# main.net
KiCad netlist of a schematic drawn in EAGLE
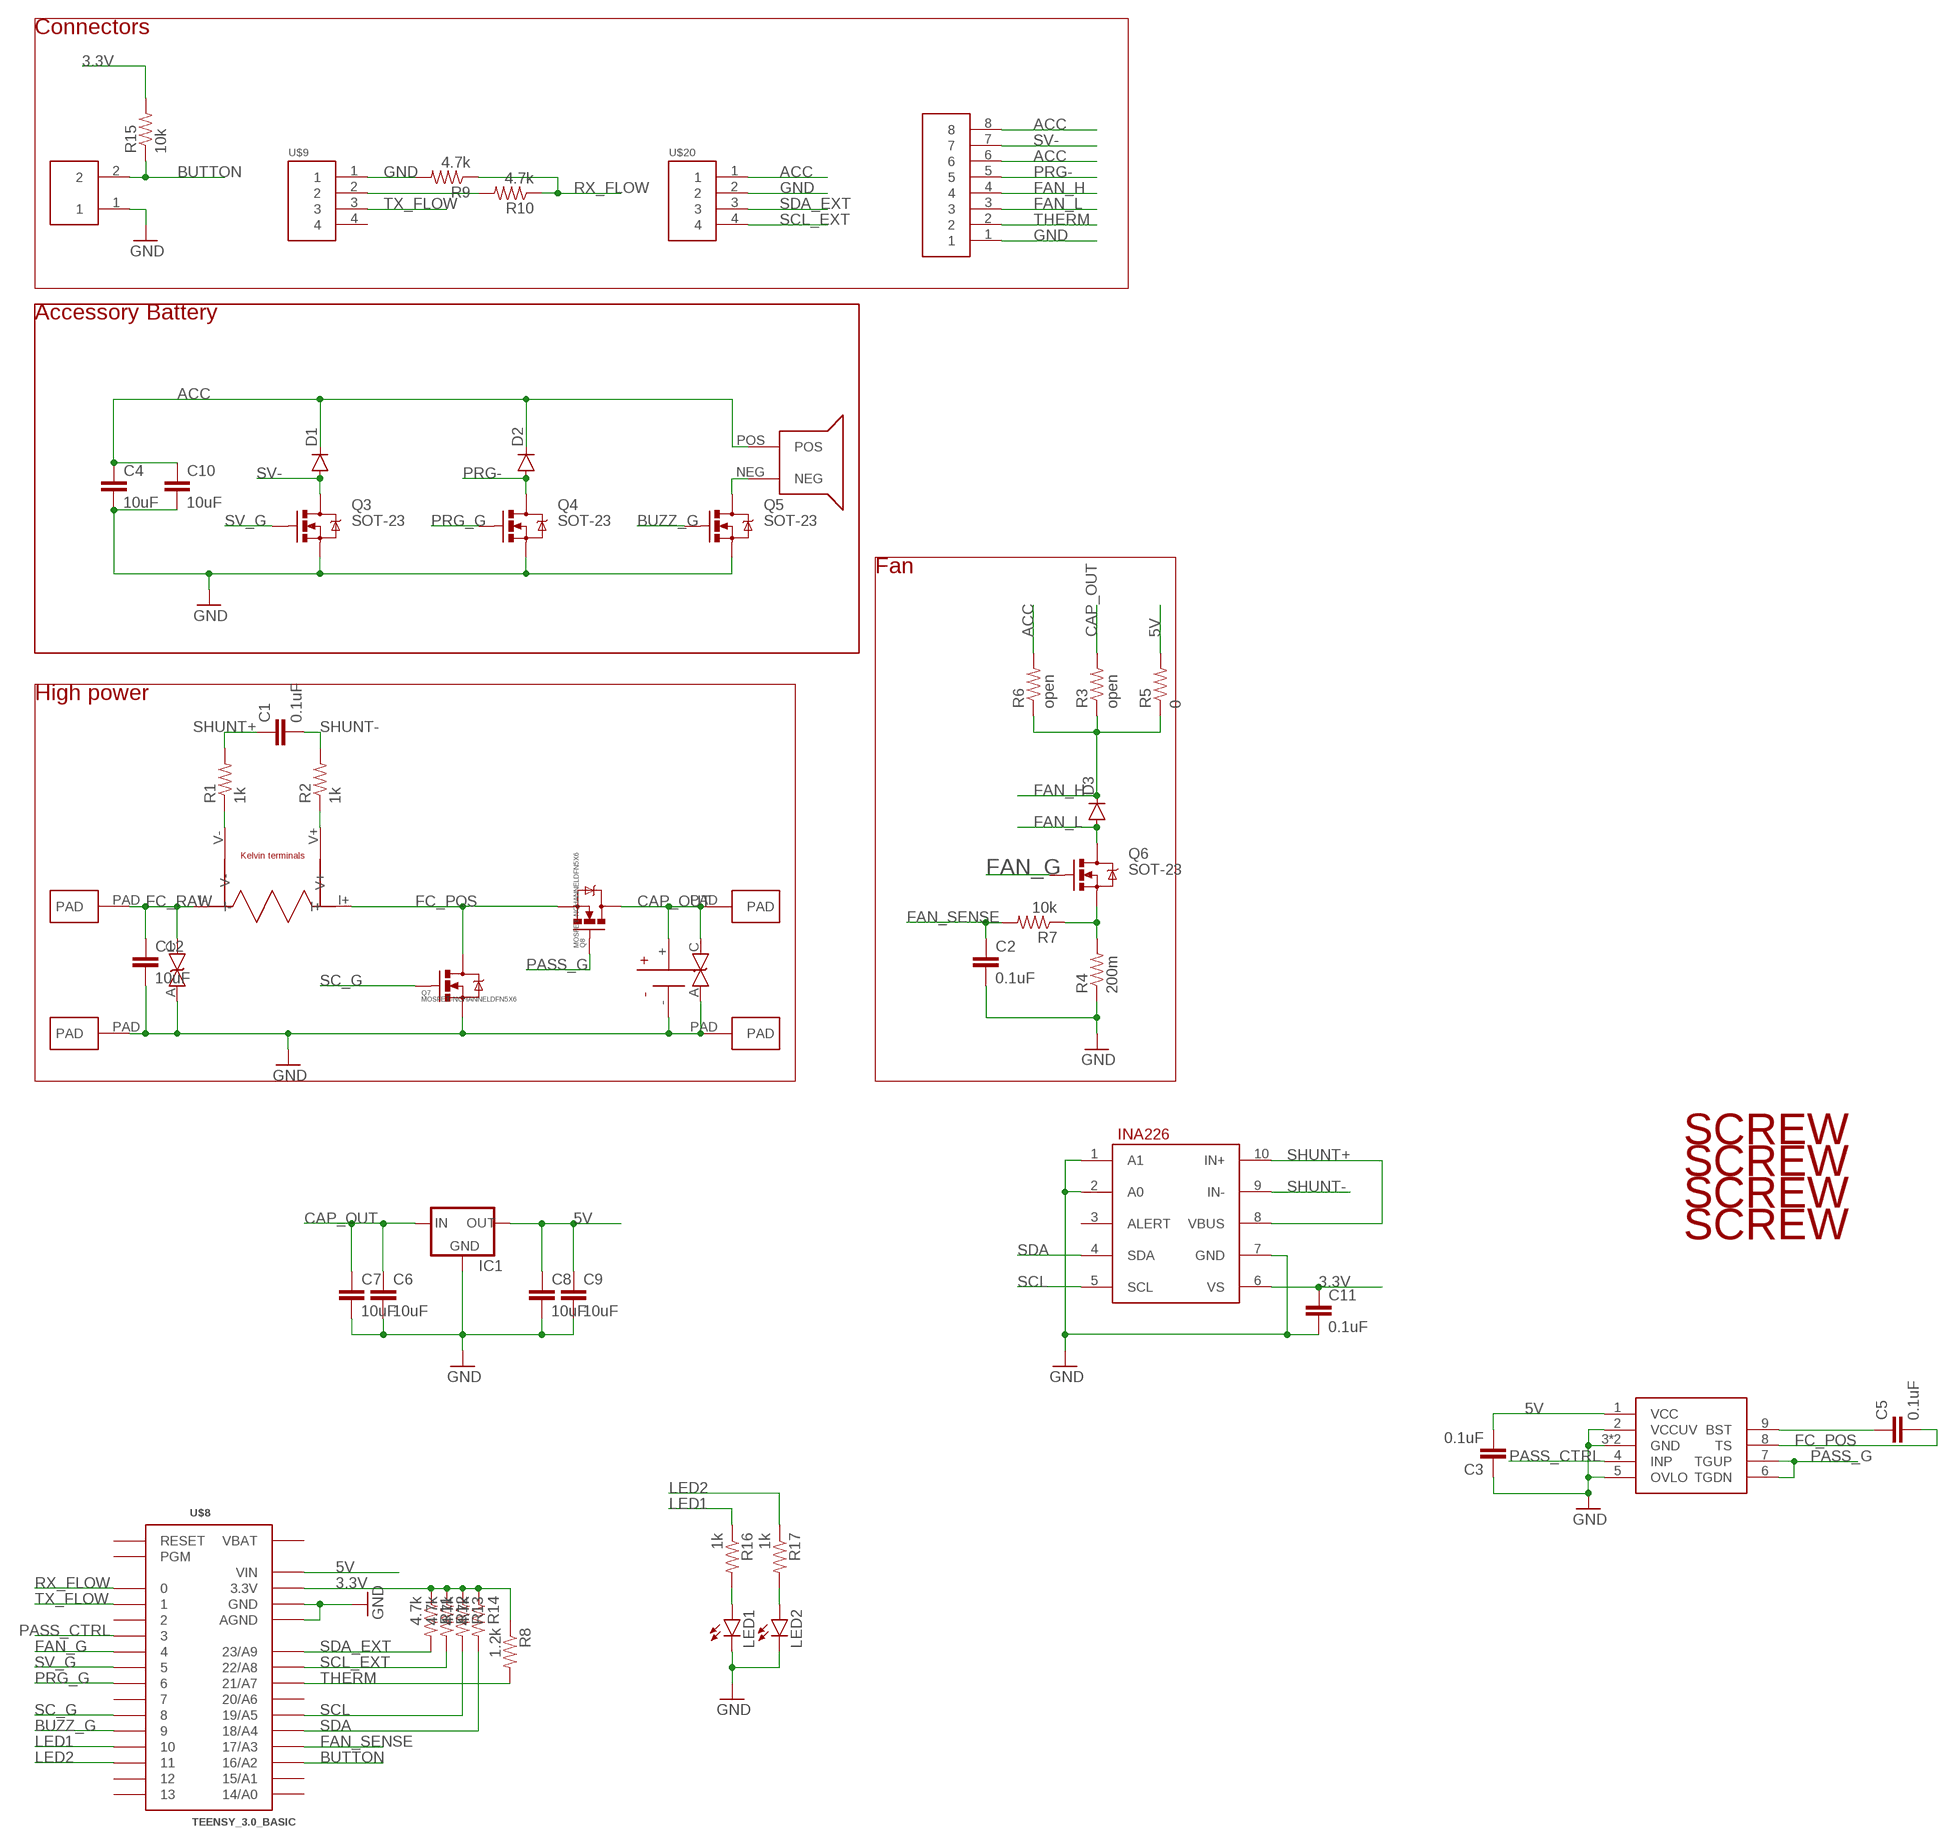
[diagram p0: schematic, sheet 1]

(export (version "E")
  (design (tool "Eeschema 10.0.6"))
  (components
    (comp (ref "C1")
      (value "0.1uF")
      (footprint "eagle-import:0603-CAP")
      (libsource (lib "eagle-import") (part "CAP0603-CAP"))
    )
    (comp (ref "C2")
      (value "0.1uF")
      (footprint "eagle-import:0603-CAP")
      (libsource (lib "eagle-import") (part "CAP0603-CAP"))
    )
    (comp (ref "C3")
      (value "0.1uF")
      (footprint "eagle-import:0603-CAP")
      (libsource (lib "eagle-import") (part "CAP0603-CAP"))
    )
    (comp (ref "C4")
      (value "10uF")
      (footprint "eagle-import:1206")
      (libsource (lib "eagle-import") (part "CAP1206"))
    )
    (comp (ref "C5")
      (value "0.1uF")
      (footprint "eagle-import:0603-CAP")
      (libsource (lib "eagle-import") (part "CAP0603-CAP"))
    )
    (comp (ref "C6")
      (value "10uF")
      (footprint "eagle-import:1206")
      (libsource (lib "eagle-import") (part "CAP1206"))
    )
    (comp (ref "C7")
      (value "10uF")
      (footprint "eagle-import:1206")
      (libsource (lib "eagle-import") (part "CAP1206"))
    )
    (comp (ref "C8")
      (value "10uF")
      (footprint "eagle-import:1206")
      (libsource (lib "eagle-import") (part "CAP1206"))
    )
    (comp (ref "C9")
      (value "10uF")
      (footprint "eagle-import:1206")
      (libsource (lib "eagle-import") (part "CAP1206"))
    )
    (comp (ref "C10")
      (value "10uF")
      (footprint "eagle-import:1206")
      (libsource (lib "eagle-import") (part "CAP1206"))
    )
    (comp (ref "C11")
      (value "0.1uF")
      (footprint "eagle-import:0603-CAP")
      (libsource (lib "eagle-import") (part "CAP0603-CAP"))
    )
    (comp (ref "C12")
      (value "10uF")
      (footprint "eagle-import:1206")
      (libsource (lib "eagle-import") (part "CAP1206"))
    )
    (comp (ref "D1")
      (value "DIODESOD123")
      (footprint "eagle-import:SOD-123")
      (libsource (lib "eagle-import") (part "DIODESOD123"))
    )
    (comp (ref "D2")
      (value "DIODESOD123")
      (footprint "eagle-import:SOD-123")
      (libsource (lib "eagle-import") (part "DIODESOD123"))
    )
    (comp (ref "D3")
      (value "DIODESOD123")
      (footprint "eagle-import:SOD-123")
      (libsource (lib "eagle-import") (part "DIODESOD123"))
    )
    (comp (ref "IC1")
      (value "V_REG_78XXV78W")
      (footprint "eagle-import:V78W")
      (libsource (lib "eagle-import") (part "V_REG_78XXV78W"))
    )
    (comp (ref "LED1")
      (value "LED1206")
      (footprint "eagle-import:LED-1206")
      (libsource (lib "eagle-import") (part "LED1206"))
    )
    (comp (ref "LED2")
      (value "LED1206")
      (footprint "eagle-import:LED-1206")
      (libsource (lib "eagle-import") (part "LED1206"))
    )
    (comp (ref "Q3")
      (value "SOT-23")
      (footprint "eagle-import:SOT23-3")
      (libsource (lib "eagle-import") (part "MOSFET-NCHANNELBSS123LT1G"))
    )
    (comp (ref "Q4")
      (value "SOT-23")
      (footprint "eagle-import:SOT23-3")
      (libsource (lib "eagle-import") (part "MOSFET-NCHANNELBSS123LT1G"))
    )
    (comp (ref "Q5")
      (value "SOT-23")
      (footprint "eagle-import:SOT23-3")
      (libsource (lib "eagle-import") (part "MOSFET-NCHANNELBSS123LT1G"))
    )
    (comp (ref "Q6")
      (value "SOT-23")
      (footprint "eagle-import:SOT23-3")
      (libsource (lib "eagle-import") (part "MOSFET-NCHANNELBSS123LT1G"))
    )
    (comp (ref "Q7")
      (value "MOSFET-NCHANNELDFN5X6")
      (footprint "eagle-import:DFN5X6")
      (libsource (lib "eagle-import") (part "MOSFET-NCHANNELDFN5X6"))
    )
    (comp (ref "Q8")
      (value "MOSFET-NCHANNELDFN5X6")
      (footprint "eagle-import:DFN5X6")
      (libsource (lib "eagle-import") (part "MOSFET-NCHANNELDFN5X6"))
    )
    (comp (ref "R1")
      (value "1k")
      (footprint "eagle-import:0603-RES")
      (libsource (lib "eagle-import") (part "RESISTOR0603-RES"))
    )
    (comp (ref "R2")
      (value "1k")
      (footprint "eagle-import:0603-RES")
      (libsource (lib "eagle-import") (part "RESISTOR0603-RES"))
    )
    (comp (ref "R3")
      (value "open")
      (footprint "eagle-import:0603-RES")
      (libsource (lib "eagle-import") (part "RESISTOR0603-RES"))
    )
    (comp (ref "R4")
      (value "200m")
      (footprint "eagle-import:0603-RES")
      (libsource (lib "eagle-import") (part "RESISTOR0603-RES"))
    )
    (comp (ref "R5")
      (value "0")
      (footprint "eagle-import:0603-RES")
      (libsource (lib "eagle-import") (part "RESISTOR0603-RES"))
    )
    (comp (ref "R6")
      (value "open")
      (footprint "eagle-import:0603-RES")
      (libsource (lib "eagle-import") (part "RESISTOR0603-RES"))
    )
    (comp (ref "R7")
      (value "10k")
      (footprint "eagle-import:0603-RES")
      (libsource (lib "eagle-import") (part "RESISTOR0603-RES"))
    )
    (comp (ref "R8")
      (value "1.2k")
      (footprint "eagle-import:0603-RES")
      (libsource (lib "eagle-import") (part "RESISTOR0603-RES"))
    )
    (comp (ref "R9")
      (value "4.7k")
      (footprint "eagle-import:0603-RES")
      (libsource (lib "eagle-import") (part "RESISTOR0603-RES"))
    )
    (comp (ref "R10")
      (value "4.7k")
      (footprint "eagle-import:0603-RES")
      (libsource (lib "eagle-import") (part "RESISTOR0603-RES"))
    )
    (comp (ref "R11")
      (value "4.7k")
      (footprint "eagle-import:0603-RES")
      (libsource (lib "eagle-import") (part "RESISTOR0603-RES"))
    )
    (comp (ref "R12")
      (value "4.7k")
      (footprint "eagle-import:0603-RES")
      (libsource (lib "eagle-import") (part "RESISTOR0603-RES"))
    )
    (comp (ref "R13")
      (value "4.7k")
      (footprint "eagle-import:0603-RES")
      (libsource (lib "eagle-import") (part "RESISTOR0603-RES"))
    )
    (comp (ref "R14")
      (value "4.7k")
      (footprint "eagle-import:0603-RES")
      (libsource (lib "eagle-import") (part "RESISTOR0603-RES"))
    )
    (comp (ref "R15")
      (value "10k")
      (footprint "eagle-import:0603-RES")
      (libsource (lib "eagle-import") (part "RESISTOR0603-RES"))
    )
    (comp (ref "R16")
      (value "1k")
      (footprint "eagle-import:0603-RES")
      (libsource (lib "eagle-import") (part "RESISTOR0603-RES"))
    )
    (comp (ref "R17")
      (value "1k")
      (footprint "eagle-import:0603-RES")
      (libsource (lib "eagle-import") (part "RESISTOR0603-RES"))
    )
    (comp (ref "U$1")
      (value "SHUNT_KELVIN")
      (footprint "eagle-import:2512_KELVIN")
      (libsource (lib "eagle-import") (part "SHUNT_KELVIN"))
    )
    (comp (ref "U$2")
      (value "INA226")
      (footprint "eagle-import:PSOP-10")
      (libsource (lib "eagle-import") (part "INA226"))
    )
    (comp (ref "U$3")
      (value "PAD")
      (footprint "eagle-import:PAD")
      (libsource (lib "eagle-import") (part "PAD"))
    )
    (comp (ref "U$4")
      (value "PAD")
      (footprint "eagle-import:PAD")
      (libsource (lib "eagle-import") (part "PAD"))
    )
    (comp (ref "U$5")
      (value "HEADER8")
      (footprint "eagle-import:8PINVALULOK")
      (libsource (lib "eagle-import") (part "HEADER8"))
    )
    (comp (ref "U$6")
      (value "LTC7001")
      (footprint "eagle-import:PSOP-10-EP")
      (libsource (lib "eagle-import") (part "LTC7001"))
    )
    (comp (ref "U$7")
      (value "BUZZER12MM")
      (footprint "eagle-import:BUZZER_12MM")
      (libsource (lib "eagle-import") (part "BUZZER12MM"))
    )
    (comp (ref "U$8")
      (value "TEENSY_3.0_BASIC")
      (footprint "eagle-import:TEENSY_3.0_BASIC")
      (libsource (lib "eagle-import") (part "TEENSY_3.0_BASIC"))
    )
    (comp (ref "U$9")
      (value "HEADER4VALULOK")
      (footprint "eagle-import:4PINVALULOK")
      (libsource (lib "eagle-import") (part "HEADER4VALULOK"))
    )
    (comp (ref "U$10")
      (value "PAD")
      (footprint "eagle-import:PAD")
      (libsource (lib "eagle-import") (part "PAD"))
    )
    (comp (ref "U$11")
      (value "PAD")
      (footprint "eagle-import:PAD")
      (libsource (lib "eagle-import") (part "PAD"))
    )
    (comp (ref "U$12")
      (value "CAP-AL_ELECTROLYTIC")
      (footprint "eagle-import:CAP-RADIAL")
      (libsource (lib "eagle-import") (part "CAP-AL_ELECTROLYTIC"))
    )
    (comp (ref "U$13")
      (value "HEADER2")
      (footprint "eagle-import:2PINVALULOK")
      (libsource (lib "eagle-import") (part "HEADER2"))
    )
    (comp (ref "U$14")
      (value "SCREW")
      (footprint "eagle-import:M3HOLE")
      (libsource (lib "eagle-import") (part "SCREW"))
    )
    (comp (ref "U$15")
      (value "SCREW")
      (footprint "eagle-import:M3HOLE")
      (libsource (lib "eagle-import") (part "SCREW"))
    )
    (comp (ref "U$16")
      (value "TVS_BIDO-214AB")
      (footprint "eagle-import:DO-214AB")
      (libsource (lib "eagle-import") (part "TVS_BIDO-214AB"))
    )
    (comp (ref "U$17")
      (value "TVS_BIDO-214AB")
      (footprint "eagle-import:DO-214AB")
      (libsource (lib "eagle-import") (part "TVS_BIDO-214AB"))
    )
    (comp (ref "U$18")
      (value "SCREW")
      (footprint "eagle-import:M3HOLE")
      (libsource (lib "eagle-import") (part "SCREW"))
    )
    (comp (ref "U$19")
      (value "SCREW")
      (footprint "eagle-import:M3HOLE")
      (libsource (lib "eagle-import") (part "SCREW"))
    )
    (comp (ref "U$20")
      (value "HEADER4VALULOK")
      (footprint "eagle-import:4PINVALULOK")
      (libsource (lib "eagle-import") (part "HEADER4VALULOK"))
    )
  )
  (nets
    (net (code "1") (name "/3.3V") (class "Default")
      (node (ref "C11") (pin "1") (pinfunction "1_1") (pintype "passive"))
      (node (ref "R11") (pin "1") (pinfunction "1_1") (pintype "passive"))
      (node (ref "R12") (pin "1") (pinfunction "1_1") (pintype "passive"))
      (node (ref "R13") (pin "1") (pinfunction "1_1") (pintype "passive"))
      (node (ref "R14") (pin "1") (pinfunction "1_1") (pintype "passive"))
      (node (ref "R15") (pin "2") (pinfunction "2_2") (pintype "passive"))
      (node (ref "R8") (pin "1") (pinfunction "1_1") (pintype "passive"))
      (node (ref "U$2") (pin "6") (pinfunction "VS_6") (pintype "bidirectional"))
      (node (ref "U$8") (pin "3.3V") (pinfunction "3.3V_3.3V") (pintype "power_in"))
      (node (ref "U$8") (pin "3.3V1") (pinfunction "3.3V_3.3V1") (pintype "power_in"))
    )
    (net (code "2") (name "/5V") (class "Default")
      (node (ref "C3") (pin "2") (pinfunction "2_2") (pintype "passive"))
      (node (ref "C8") (pin "1") (pinfunction "1_1") (pintype "passive"))
      (node (ref "C9") (pin "1") (pinfunction "1_1") (pintype "passive"))
      (node (ref "IC1") (pin "OUT") (pinfunction "OUT_OUT") (pintype "output"))
      (node (ref "R5") (pin "2") (pinfunction "2_2") (pintype "passive"))
      (node (ref "U$6") (pin "1") (pinfunction "VCC_1") (pintype "bidirectional"))
      (node (ref "U$8") (pin "VIN") (pinfunction "VIN_VIN") (pintype "power_in"))
    )
    (net (code "3") (name "/ACC") (class "Default")
      (node (ref "C10") (pin "1") (pinfunction "1_1") (pintype "passive"))
      (node (ref "C4") (pin "1") (pinfunction "1_1") (pintype "passive"))
      (node (ref "D1") (pin "C") (pinfunction "C_C") (pintype "passive"))
      (node (ref "D2") (pin "C") (pinfunction "C_C") (pintype "passive"))
      (node (ref "R6") (pin "2") (pinfunction "2_2") (pintype "passive"))
      (node (ref "U$20") (pin "1") (pinfunction "1_1") (pintype "bidirectional"))
      (node (ref "U$5") (pin "6") (pinfunction "6_6") (pintype "bidirectional"))
      (node (ref "U$5") (pin "8") (pinfunction "8_8") (pintype "bidirectional"))
      (node (ref "U$7") (pin "POS") (pinfunction "POS_POS") (pintype "bidirectional"))
    )
    (net (code "4") (name "/BUTTON") (class "Default")
      (node (ref "R15") (pin "1") (pinfunction "1_1") (pintype "passive"))
      (node (ref "U$13") (pin "2") (pinfunction "2_2") (pintype "bidirectional"))
      (node (ref "U$8") (pin "16/A2") (pinfunction "16/A2_16/A2") (pintype "bidirectional"))
    )
    (net (code "5") (name "/BUZZ_G") (class "Default")
      (node (ref "Q5") (pin "1") (pinfunction "G_1") (pintype "passive"))
      (node (ref "U$8") (pin "9") (pinfunction "9_9") (pintype "bidirectional"))
    )
    (net (code "6") (name "/CAP_OUT") (class "Default")
      (node (ref "C6") (pin "1") (pinfunction "1_1") (pintype "passive"))
      (node (ref "C7") (pin "1") (pinfunction "1_1") (pintype "passive"))
      (node (ref "IC1") (pin "IN") (pinfunction "IN_IN") (pintype "input"))
      (node (ref "Q8") (pin "PAD") (pinfunction "D_PAD") (pintype "passive"))
      (node (ref "R3") (pin "2") (pinfunction "2_2") (pintype "passive"))
      (node (ref "U$10") (pin "PAD") (pinfunction "PAD_PAD") (pintype "bidirectional"))
      (node (ref "U$12") (pin "+") (pinfunction "V+_+") (pintype "bidirectional"))
      (node (ref "U$17") (pin "C") (pinfunction "2_C") (pintype "bidirectional"))
    )
    (net (code "7") (name "/FAN_G") (class "Default")
      (node (ref "Q6") (pin "1") (pinfunction "G_1") (pintype "passive"))
      (node (ref "U$8") (pin "4") (pinfunction "4_4") (pintype "bidirectional"))
    )
    (net (code "8") (name "/FAN_H") (class "Default")
      (node (ref "D3") (pin "C") (pinfunction "C_C") (pintype "passive"))
      (node (ref "R3") (pin "1") (pinfunction "1_1") (pintype "passive"))
      (node (ref "R5") (pin "1") (pinfunction "1_1") (pintype "passive"))
      (node (ref "R6") (pin "1") (pinfunction "1_1") (pintype "passive"))
      (node (ref "U$5") (pin "4") (pinfunction "4_4") (pintype "bidirectional"))
    )
    (net (code "9") (name "/FAN_L") (class "Default")
      (node (ref "D3") (pin "A") (pinfunction "A_A") (pintype "passive"))
      (node (ref "Q6") (pin "3") (pinfunction "D_3") (pintype "passive"))
      (node (ref "U$5") (pin "3") (pinfunction "3_3") (pintype "bidirectional"))
    )
    (net (code "10") (name "/FAN_SENSE") (class "Default")
      (node (ref "C2") (pin "1") (pinfunction "1_1") (pintype "passive"))
      (node (ref "R7") (pin "2") (pinfunction "2_2") (pintype "passive"))
      (node (ref "U$8") (pin "17/A3") (pinfunction "17/A3_17/A3") (pintype "bidirectional"))
    )
    (net (code "11") (name "/FC_POS") (class "Default")
      (node (ref "C5") (pin "2") (pinfunction "2_2") (pintype "passive"))
      (node (ref "Q7") (pin "PAD") (pinfunction "D_PAD") (pintype "passive"))
      (node (ref "Q8") (pin "1") (pinfunction "S_1") (pintype "passive"))
      (node (ref "Q8") (pin "2") (pinfunction "S_2") (pintype "passive"))
      (node (ref "Q8") (pin "3") (pinfunction "S_3") (pintype "passive"))
      (node (ref "U$1") (pin "I+") (pinfunction "I+_I+") (pintype "bidirectional"))
      (node (ref "U$6") (pin "8") (pinfunction "TS_8") (pintype "bidirectional"))
    )
    (net (code "12") (name "/FC_RAW") (class "Default")
      (node (ref "C12") (pin "1") (pinfunction "1_1") (pintype "passive"))
      (node (ref "U$1") (pin "I-") (pinfunction "I-_I-") (pintype "bidirectional"))
      (node (ref "U$16") (pin "C") (pinfunction "2_C") (pintype "bidirectional"))
      (node (ref "U$3") (pin "PAD") (pinfunction "PAD_PAD") (pintype "bidirectional"))
    )
    (net (code "13") (name "/LED1") (class "Default")
      (node (ref "R16") (pin "1") (pinfunction "1_1") (pintype "passive"))
      (node (ref "U$8") (pin "10") (pinfunction "10_10") (pintype "bidirectional"))
    )
    (net (code "14") (name "/LED2") (class "Default")
      (node (ref "R17") (pin "1") (pinfunction "1_1") (pintype "passive"))
      (node (ref "U$8") (pin "11") (pinfunction "11_11") (pintype "bidirectional"))
    )
    (net (code "15") (name "/PASS_CTRL") (class "Default")
      (node (ref "U$6") (pin "4") (pinfunction "INP_4") (pintype "bidirectional"))
      (node (ref "U$8") (pin "3") (pinfunction "3_3") (pintype "bidirectional"))
    )
    (net (code "16") (name "/PASS_G") (class "Default")
      (node (ref "Q8") (pin "4") (pinfunction "G_4") (pintype "passive"))
      (node (ref "U$6") (pin "6") (pinfunction "TGDN_6") (pintype "bidirectional"))
      (node (ref "U$6") (pin "7") (pinfunction "TGUP_7") (pintype "bidirectional"))
    )
    (net (code "17") (name "/PRG-") (class "Default")
      (node (ref "D2") (pin "A") (pinfunction "A_A") (pintype "passive"))
      (node (ref "Q4") (pin "3") (pinfunction "D_3") (pintype "passive"))
      (node (ref "U$5") (pin "5") (pinfunction "5_5") (pintype "bidirectional"))
    )
    (net (code "18") (name "/PRG_G") (class "Default")
      (node (ref "Q4") (pin "1") (pinfunction "G_1") (pintype "passive"))
      (node (ref "U$8") (pin "6") (pinfunction "6_6") (pintype "bidirectional"))
    )
    (net (code "19") (name "/RX_FLOW") (class "Default")
      (node (ref "R10") (pin "1") (pinfunction "1_1") (pintype "passive"))
      (node (ref "R9") (pin "1") (pinfunction "1_1") (pintype "passive"))
      (node (ref "U$8") (pin "0") (pinfunction "0_0") (pintype "bidirectional"))
    )
    (net (code "20") (name "/SCL") (class "Default")
      (node (ref "R13") (pin "2") (pinfunction "2_2") (pintype "passive"))
      (node (ref "U$2") (pin "5") (pinfunction "SCL_5") (pintype "bidirectional"))
      (node (ref "U$8") (pin "19/A5") (pinfunction "19/A5_19/A5") (pintype "bidirectional"))
    )
    (net (code "21") (name "/SCL_EXT") (class "Default")
      (node (ref "R12") (pin "2") (pinfunction "2_2") (pintype "passive"))
      (node (ref "U$20") (pin "4") (pinfunction "4_4") (pintype "bidirectional"))
      (node (ref "U$8") (pin "22/A8") (pinfunction "22/A8_22/A8") (pintype "bidirectional"))
    )
    (net (code "22") (name "/SC_G") (class "Default")
      (node (ref "Q7") (pin "4") (pinfunction "G_4") (pintype "passive"))
      (node (ref "U$8") (pin "8") (pinfunction "8_8") (pintype "bidirectional"))
    )
    (net (code "23") (name "/SDA") (class "Default")
      (node (ref "R14") (pin "2") (pinfunction "2_2") (pintype "passive"))
      (node (ref "U$2") (pin "4") (pinfunction "SDA_4") (pintype "bidirectional"))
      (node (ref "U$8") (pin "18/A4") (pinfunction "18/A4_18/A4") (pintype "bidirectional"))
    )
    (net (code "24") (name "/SDA_EXT") (class "Default")
      (node (ref "R11") (pin "2") (pinfunction "2_2") (pintype "passive"))
      (node (ref "U$20") (pin "3") (pinfunction "3_3") (pintype "bidirectional"))
      (node (ref "U$8") (pin "23/A9") (pinfunction "23/A9_23/A9") (pintype "bidirectional"))
    )
    (net (code "25") (name "/SHUNT+") (class "Default")
      (node (ref "C1") (pin "1") (pinfunction "1_1") (pintype "passive"))
      (node (ref "R1") (pin "2") (pinfunction "2_2") (pintype "passive"))
      (node (ref "U$2") (pin "10") (pinfunction "IN+_10") (pintype "bidirectional"))
      (node (ref "U$2") (pin "8") (pinfunction "VBUS_8") (pintype "bidirectional"))
    )
    (net (code "26") (name "/SHUNT-") (class "Default")
      (node (ref "C1") (pin "2") (pinfunction "2_2") (pintype "passive"))
      (node (ref "R2") (pin "2") (pinfunction "2_2") (pintype "passive"))
      (node (ref "U$2") (pin "9") (pinfunction "IN-_9") (pintype "bidirectional"))
    )
    (net (code "27") (name "/SV-") (class "Default")
      (node (ref "D1") (pin "A") (pinfunction "A_A") (pintype "passive"))
      (node (ref "Q3") (pin "3") (pinfunction "D_3") (pintype "passive"))
      (node (ref "U$5") (pin "7") (pinfunction "7_7") (pintype "bidirectional"))
    )
    (net (code "28") (name "/SV_G") (class "Default")
      (node (ref "Q3") (pin "1") (pinfunction "G_1") (pintype "passive"))
      (node (ref "U$8") (pin "5") (pinfunction "5_5") (pintype "bidirectional"))
    )
    (net (code "29") (name "/THERM") (class "Default")
      (node (ref "R8") (pin "2") (pinfunction "2_2") (pintype "passive"))
      (node (ref "U$5") (pin "2") (pinfunction "2_2") (pintype "bidirectional"))
      (node (ref "U$8") (pin "21/A7") (pinfunction "21/A7_21/A7") (pintype "bidirectional"))
    )
    (net (code "30") (name "/TX_FLOW") (class "Default")
      (node (ref "U$8") (pin "1") (pinfunction "1_1") (pintype "bidirectional"))
      (node (ref "U$9") (pin "3") (pinfunction "3_3") (pintype "bidirectional"))
    )
    (net (code "31") (name "/VBAT") (class "Default")
      (node (ref "U$8") (pin "VBAT") (pinfunction "VBAT_VBAT") (pintype "power_in"))
    )
    (net (code "32") (name "GND") (class "Default")
      (node (ref "C10") (pin "2") (pinfunction "2_2") (pintype "passive"))
      (node (ref "C11") (pin "2") (pinfunction "2_2") (pintype "passive"))
      (node (ref "C12") (pin "2") (pinfunction "2_2") (pintype "passive"))
      (node (ref "C2") (pin "2") (pinfunction "2_2") (pintype "passive"))
      (node (ref "C3") (pin "1") (pinfunction "1_1") (pintype "passive"))
      (node (ref "C4") (pin "2") (pinfunction "2_2") (pintype "passive"))
      (node (ref "C6") (pin "2") (pinfunction "2_2") (pintype "passive"))
      (node (ref "C7") (pin "2") (pinfunction "2_2") (pintype "passive"))
      (node (ref "C8") (pin "2") (pinfunction "2_2") (pintype "passive"))
      (node (ref "C9") (pin "2") (pinfunction "2_2") (pintype "passive"))
      (node (ref "IC1") (pin "GND") (pinfunction "GND_GND") (pintype "input"))
      (node (ref "LED1") (pin "C") (pinfunction "C_C") (pintype "passive"))
      (node (ref "LED2") (pin "C") (pinfunction "C_C") (pintype "passive"))
      (node (ref "Q3") (pin "2") (pinfunction "S_2") (pintype "passive"))
      (node (ref "Q4") (pin "2") (pinfunction "S_2") (pintype "passive"))
      (node (ref "Q5") (pin "2") (pinfunction "S_2") (pintype "passive"))
      (node (ref "Q7") (pin "1") (pinfunction "S_1") (pintype "passive"))
      (node (ref "Q7") (pin "2") (pinfunction "S_2") (pintype "passive"))
      (node (ref "Q7") (pin "3") (pinfunction "S_3") (pintype "passive"))
      (node (ref "R4") (pin "1") (pinfunction "1_1") (pintype "passive"))
      (node (ref "R9") (pin "2") (pinfunction "2_2") (pintype "passive"))
      (node (ref "U$11") (pin "PAD") (pinfunction "PAD_PAD") (pintype "bidirectional"))
      (node (ref "U$12") (pin "-") (pinfunction "V-_-") (pintype "bidirectional"))
      (node (ref "U$13") (pin "1") (pinfunction "1_1") (pintype "bidirectional"))
      (node (ref "U$16") (pin "A") (pinfunction "1_A") (pintype "bidirectional"))
      (node (ref "U$17") (pin "A") (pinfunction "1_A") (pintype "bidirectional"))
      (node (ref "U$2") (pin "1") (pinfunction "A1_1") (pintype "bidirectional"))
      (node (ref "U$2") (pin "2") (pinfunction "A0_2") (pintype "bidirectional"))
      (node (ref "U$2") (pin "7") (pinfunction "GND_7") (pintype "bidirectional"))
      (node (ref "U$20") (pin "2") (pinfunction "2_2") (pintype "bidirectional"))
      (node (ref "U$4") (pin "PAD") (pinfunction "PAD_PAD") (pintype "bidirectional"))
      (node (ref "U$5") (pin "1") (pinfunction "1_1") (pintype "bidirectional"))
      (node (ref "U$6") (pin "2") (pinfunction "VCCUV_2") (pintype "bidirectional"))
      (node (ref "U$6") (pin "3") (pinfunction "GND_3") (pintype "bidirectional"))
      (node (ref "U$6") (pin "5") (pinfunction "OVLO_5") (pintype "bidirectional"))
      (node (ref "U$6") (pin "PAD") (pinfunction "GND_PAD") (pintype "bidirectional"))
      (node (ref "U$8") (pin "AGND") (pinfunction "AGND_AGND") (pintype "power_in"))
      (node (ref "U$8") (pin "GND") (pinfunction "GND_GND") (pintype "power_in"))
      (node (ref "U$8") (pin "GND1") (pinfunction "GND_GND1") (pintype "power_in"))
      (node (ref "U$9") (pin "1") (pinfunction "1_1") (pintype "bidirectional"))
    )
    (net (code "33") (name "Net-(LED1-PadA)") (class "Default")
      (node (ref "LED1") (pin "A") (pinfunction "A_A") (pintype "passive"))
      (node (ref "R16") (pin "2") (pinfunction "2_2") (pintype "passive"))
    )
    (net (code "34") (name "Net-(LED2-PadA)") (class "Default")
      (node (ref "LED2") (pin "A") (pinfunction "A_A") (pintype "passive"))
      (node (ref "R17") (pin "2") (pinfunction "2_2") (pintype "passive"))
    )
    (net (code "35") (name "Net-(Q5-D)") (class "Default")
      (node (ref "Q5") (pin "3") (pinfunction "D_3") (pintype "passive"))
      (node (ref "U$7") (pin "NEG") (pinfunction "NEG_NEG") (pintype "bidirectional"))
    )
    (net (code "36") (name "Net-(Q6-S)") (class "Default")
      (node (ref "Q6") (pin "2") (pinfunction "S_2") (pintype "passive"))
      (node (ref "R4") (pin "2") (pinfunction "2_2") (pintype "passive"))
      (node (ref "R7") (pin "1") (pinfunction "1_1") (pintype "passive"))
    )
    (net (code "37") (name "Net-(R1-Pad1)") (class "Default")
      (node (ref "R1") (pin "1") (pinfunction "1_1") (pintype "passive"))
      (node (ref "U$1") (pin "V-") (pinfunction "V-_V-") (pintype "bidirectional"))
    )
    (net (code "38") (name "Net-(R2-Pad1)") (class "Default")
      (node (ref "R2") (pin "1") (pinfunction "1_1") (pintype "passive"))
      (node (ref "U$1") (pin "V+") (pinfunction "V+_V+") (pintype "bidirectional"))
    )
    (net (code "39") (name "Net-(R10-Pad2)") (class "Default")
      (node (ref "R10") (pin "2") (pinfunction "2_2") (pintype "passive"))
      (node (ref "U$9") (pin "2") (pinfunction "2_2") (pintype "bidirectional"))
    )
    (net (code "40") (name "Net-(U$6-BST)") (class "Default")
      (node (ref "C5") (pin "1") (pinfunction "1_1") (pintype "passive"))
      (node (ref "U$6") (pin "9") (pinfunction "BST_9") (pintype "bidirectional"))
    )
    (net (code "41") (name "unconnected-(U$2-ALERT-Pad3)") (class "Default")
      (node (ref "U$2") (pin "3") (pinfunction "ALERT_3") (pintype "bidirectional"))
    )
    (net (code "42") (name "unconnected-(U$8-Pad2)") (class "Default")
      (node (ref "U$8") (pin "2") (pinfunction "2_2") (pintype "bidirectional"))
    )
    (net (code "43") (name "unconnected-(U$8-Pad7)") (class "Default")
      (node (ref "U$8") (pin "7") (pinfunction "7_7") (pintype "bidirectional"))
    )
    (net (code "44") (name "unconnected-(U$8-Pad12)") (class "Default")
      (node (ref "U$8") (pin "12") (pinfunction "12_12") (pintype "bidirectional"))
    )
    (net (code "45") (name "unconnected-(U$8-Pad13)") (class "Default")
      (node (ref "U$8") (pin "13") (pinfunction "13_13") (pintype "bidirectional"))
    )
    (net (code "46") (name "unconnected-(U$8-Pad14{slash}A0)") (class "Default")
      (node (ref "U$8") (pin "14/A0") (pinfunction "14/A0_14/A0") (pintype "bidirectional"))
    )
    (net (code "47") (name "unconnected-(U$8-Pad15{slash}A1)") (class "Default")
      (node (ref "U$8") (pin "15/A1") (pinfunction "15/A1_15/A1") (pintype "bidirectional"))
    )
    (net (code "48") (name "unconnected-(U$8-Pad20{slash}A6)") (class "Default")
      (node (ref "U$8") (pin "20/A6") (pinfunction "20/A6_20/A6") (pintype "bidirectional"))
    )
    (net (code "49") (name "unconnected-(U$8-PadPGM)") (class "Default")
      (node (ref "U$8") (pin "PGM") (pinfunction "PGM_PGM") (pintype "bidirectional"))
    )
    (net (code "50") (name "unconnected-(U$8-PadRESET)") (class "Default")
      (node (ref "U$8") (pin "RESET") (pinfunction "RESET_RESET") (pintype "bidirectional"))
    )
    (net (code "51") (name "unconnected-(U$9-Pad4)") (class "Default")
      (node (ref "U$9") (pin "4") (pinfunction "4_4") (pintype "bidirectional"))
    )
  )
)
